# euu.net
KiCad netlist of a schematic drawn in Altium Designer
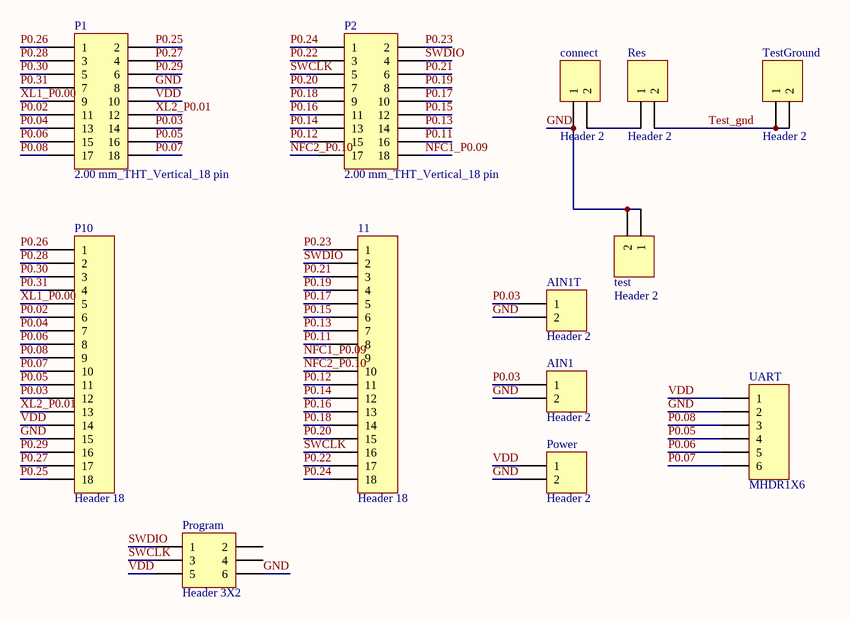
[diagram p0: euu.SchDoc]

(export (version "E")
  (design (tool "Eeschema 10.0.6"))
  (components
    (comp (ref "11")
      (value "Header 18")
      (footprint "HDR1X18")
      (description "Header, 18-Pin")
      (fields (field (name "PUBLISHER") "Altium Limited"))
      (libsource (lib "Miscellaneous Connectors") (part "Header 18"))
    )
    (comp (ref "AIN1")
      (value "Header 2")
      (footprint "HDR1X2")
      (description "Header, 2-Pin")
      (fields (field (name "PUBLISHER") "Altium Limited"))
      (libsource (lib "") (part "Header 2_1"))
    )
    (comp (ref "AIN1T")
      (value "Header 2")
      (footprint "HDR1X2")
      (description "Header, 2-Pin")
      (fields (field (name "PUBLISHER") "Altium Limited"))
      (libsource (lib "") (part "Header 2_1"))
    )
    (comp (ref "connect")
      (value "Header 2")
      (footprint "HDR1X2")
      (description "Header, 2-Pin")
      (fields (field (name "PUBLISHER") "Altium Limited"))
      (libsource (lib "Miscellaneous Connectors") (part "Header 2"))
    )
    (comp (ref "P1")
      (value "2.00 mm_THT_Vertical_18 pin")
      (footprint "header:Header9x2")
      (description "Header, 9-Pin, Dual row")
      (fields (field (name "PUBLISHER") "Altium Limited"))
      (libsource (lib "Miscellaneous Connectors") (part "Header 9X2"))
    )
    (comp (ref "P2")
      (value "2.00 mm_THT_Vertical_18 pin")
      (footprint "header:Header9x2")
      (description "Header, 9-Pin, Dual row")
      (fields (field (name "PUBLISHER") "Altium Limited"))
      (libsource (lib "Miscellaneous Connectors") (part "Header 9X2"))
    )
    (comp (ref "P10")
      (value "Header 18")
      (footprint "HDR1X18")
      (description "Header, 18-Pin")
      (fields (field (name "PUBLISHER") "Altium Limited"))
      (libsource (lib "Miscellaneous Connectors") (part "Header 18"))
    )
    (comp (ref "Power")
      (value "Header 2")
      (footprint "HDR1X2")
      (description "Header, 2-Pin")
      (fields (field (name "PUBLISHER") "Altium Limited"))
      (libsource (lib "") (part "Header 2_1"))
    )
    (comp (ref "Program")
      (value "Header 3X2")
      (footprint "HDR2X3")
      (description "Header, 3-Pin, Dual row")
      (fields (field (name "PUBLISHER") "Altium Limited"))
      (libsource (lib "Miscellaneous Connectors") (part "Header 3X2"))
    )
    (comp (ref "Res")
      (value "Header 2")
      (footprint "HDR1X2")
      (description "Header, 2-Pin")
      (fields (field (name "PUBLISHER") "Altium Limited"))
      (libsource (lib "Miscellaneous Connectors") (part "Header 2"))
    )
    (comp (ref "test")
      (value "Header 2")
      (footprint "HDR1X2")
      (description "Header, 2-Pin")
      (fields (field (name "PUBLISHER") "Altium Limited"))
      (libsource (lib "") (part "Header 2_2"))
    )
    (comp (ref "TestGround")
      (value "Header 2")
      (footprint "HDR1X2")
      (description "Header, 2-Pin")
      (fields (field (name "PUBLISHER") "Altium Limited"))
      (libsource (lib "Miscellaneous Connectors") (part "Header 2"))
    )
    (comp (ref "UART")
      (value "MHDR1X6")
      (footprint "header:HEADER6")
      (description "Header, 6-Pin")
      (fields (field (name "PUBLISHER") "Altium Limited"))
      (libsource (lib "Miscellaneous Connectors") (part "MHDR1X6"))
    )
  )
  (nets
    (net (code "1") (name "/GND") (class "Default")
      (node (ref "AIN1") (pin "2") (pinfunction "2_2") (pintype "passive"))
      (node (ref "AIN1T") (pin "2") (pinfunction "2_2") (pintype "passive"))
      (node (ref "P1") (pin "8") (pinfunction "8_8") (pintype "passive"))
      (node (ref "P10") (pin "15") (pinfunction "15_15") (pintype "passive"))
      (node (ref "Power") (pin "2") (pinfunction "2_2") (pintype "passive"))
      (node (ref "Program") (pin "6") (pinfunction "6_6") (pintype "passive"))
      (node (ref "UART") (pin "2") (pinfunction "2_2") (pintype "passive"))
      (node (ref "connect") (pin "1") (pinfunction "1_1") (pintype "passive"))
      (node (ref "test") (pin "1") (pinfunction "1_1") (pintype "passive"))
      (node (ref "test") (pin "2") (pinfunction "2_2") (pintype "passive"))
    )
    (net (code "2") (name "/NFC1_P0.09") (class "Default")
      (node (ref "11") (pin "9") (pinfunction "9_9") (pintype "passive"))
      (node (ref "P2") (pin "18") (pinfunction "18_18") (pintype "passive"))
    )
    (net (code "3") (name "/NFC2_P0.10") (class "Default")
      (node (ref "11") (pin "10") (pinfunction "10_10") (pintype "passive"))
      (node (ref "P2") (pin "17") (pinfunction "17_17") (pintype "passive"))
    )
    (net (code "4") (name "/P0.02") (class "Default")
      (node (ref "P1") (pin "11") (pinfunction "11_11") (pintype "passive"))
      (node (ref "P10") (pin "6") (pinfunction "6_6") (pintype "passive"))
    )
    (net (code "5") (name "/P0.03") (class "Default")
      (node (ref "AIN1") (pin "1") (pinfunction "1_1") (pintype "passive"))
      (node (ref "AIN1T") (pin "1") (pinfunction "1_1") (pintype "passive"))
      (node (ref "P1") (pin "14") (pinfunction "14_14") (pintype "passive"))
      (node (ref "P10") (pin "12") (pinfunction "12_12") (pintype "passive"))
    )
    (net (code "6") (name "/P0.04") (class "Default")
      (node (ref "P1") (pin "13") (pinfunction "13_13") (pintype "passive"))
      (node (ref "P10") (pin "7") (pinfunction "7_7") (pintype "passive"))
    )
    (net (code "7") (name "/P0.05") (class "Default")
      (node (ref "P1") (pin "16") (pinfunction "16_16") (pintype "passive"))
      (node (ref "P10") (pin "11") (pinfunction "11_11") (pintype "passive"))
      (node (ref "UART") (pin "4") (pinfunction "4_4") (pintype "passive"))
    )
    (net (code "8") (name "/P0.06") (class "Default")
      (node (ref "P1") (pin "15") (pinfunction "15_15") (pintype "passive"))
      (node (ref "P10") (pin "8") (pinfunction "8_8") (pintype "passive"))
      (node (ref "UART") (pin "5") (pinfunction "5_5") (pintype "passive"))
    )
    (net (code "9") (name "/P0.07") (class "Default")
      (node (ref "P1") (pin "18") (pinfunction "18_18") (pintype "passive"))
      (node (ref "P10") (pin "10") (pinfunction "10_10") (pintype "passive"))
      (node (ref "UART") (pin "6") (pinfunction "6_6") (pintype "passive"))
    )
    (net (code "10") (name "/P0.08") (class "Default")
      (node (ref "P1") (pin "17") (pinfunction "17_17") (pintype "passive"))
      (node (ref "P10") (pin "9") (pinfunction "9_9") (pintype "passive"))
      (node (ref "UART") (pin "3") (pinfunction "3_3") (pintype "passive"))
    )
    (net (code "11") (name "/P0.11") (class "Default")
      (node (ref "11") (pin "8") (pinfunction "8_8") (pintype "passive"))
      (node (ref "P2") (pin "16") (pinfunction "16_16") (pintype "passive"))
    )
    (net (code "12") (name "/P0.12") (class "Default")
      (node (ref "11") (pin "11") (pinfunction "11_11") (pintype "passive"))
      (node (ref "P2") (pin "15") (pinfunction "15_15") (pintype "passive"))
    )
    (net (code "13") (name "/P0.13") (class "Default")
      (node (ref "11") (pin "7") (pinfunction "7_7") (pintype "passive"))
      (node (ref "P2") (pin "14") (pinfunction "14_14") (pintype "passive"))
    )
    (net (code "14") (name "/P0.14") (class "Default")
      (node (ref "11") (pin "12") (pinfunction "12_12") (pintype "passive"))
      (node (ref "P2") (pin "13") (pinfunction "13_13") (pintype "passive"))
    )
    (net (code "15") (name "/P0.15") (class "Default")
      (node (ref "11") (pin "6") (pinfunction "6_6") (pintype "passive"))
      (node (ref "P2") (pin "12") (pinfunction "12_12") (pintype "passive"))
    )
    (net (code "16") (name "/P0.16") (class "Default")
      (node (ref "11") (pin "13") (pinfunction "13_13") (pintype "passive"))
      (node (ref "P2") (pin "11") (pinfunction "11_11") (pintype "passive"))
    )
    (net (code "17") (name "/P0.17") (class "Default")
      (node (ref "11") (pin "5") (pinfunction "5_5") (pintype "passive"))
      (node (ref "P2") (pin "10") (pinfunction "10_10") (pintype "passive"))
    )
    (net (code "18") (name "/P0.18") (class "Default")
      (node (ref "11") (pin "14") (pinfunction "14_14") (pintype "passive"))
      (node (ref "P2") (pin "9") (pinfunction "9_9") (pintype "passive"))
    )
    (net (code "19") (name "/P0.19") (class "Default")
      (node (ref "11") (pin "4") (pinfunction "4_4") (pintype "passive"))
      (node (ref "P2") (pin "8") (pinfunction "8_8") (pintype "passive"))
    )
    (net (code "20") (name "/P0.20") (class "Default")
      (node (ref "11") (pin "15") (pinfunction "15_15") (pintype "passive"))
      (node (ref "P2") (pin "7") (pinfunction "7_7") (pintype "passive"))
    )
    (net (code "21") (name "/P0.21") (class "Default")
      (node (ref "11") (pin "3") (pinfunction "3_3") (pintype "passive"))
      (node (ref "P2") (pin "6") (pinfunction "6_6") (pintype "passive"))
    )
    (net (code "22") (name "/P0.22") (class "Default")
      (node (ref "11") (pin "17") (pinfunction "17_17") (pintype "passive"))
      (node (ref "P2") (pin "3") (pinfunction "3_3") (pintype "passive"))
    )
    (net (code "23") (name "/P0.23") (class "Default")
      (node (ref "11") (pin "1") (pinfunction "1_1") (pintype "passive"))
      (node (ref "P2") (pin "2") (pinfunction "2_2") (pintype "passive"))
    )
    (net (code "24") (name "/P0.24") (class "Default")
      (node (ref "11") (pin "18") (pinfunction "18_18") (pintype "passive"))
      (node (ref "P2") (pin "1") (pinfunction "1_1") (pintype "passive"))
    )
    (net (code "25") (name "/P0.25") (class "Default")
      (node (ref "P1") (pin "2") (pinfunction "2_2") (pintype "passive"))
      (node (ref "P10") (pin "18") (pinfunction "18_18") (pintype "passive"))
    )
    (net (code "26") (name "/P0.26") (class "Default")
      (node (ref "P1") (pin "1") (pinfunction "1_1") (pintype "passive"))
      (node (ref "P10") (pin "1") (pinfunction "1_1") (pintype "passive"))
    )
    (net (code "27") (name "/P0.27") (class "Default")
      (node (ref "P1") (pin "4") (pinfunction "4_4") (pintype "passive"))
      (node (ref "P10") (pin "17") (pinfunction "17_17") (pintype "passive"))
    )
    (net (code "28") (name "/P0.28") (class "Default")
      (node (ref "P1") (pin "3") (pinfunction "3_3") (pintype "passive"))
      (node (ref "P10") (pin "2") (pinfunction "2_2") (pintype "passive"))
    )
    (net (code "29") (name "/P0.29") (class "Default")
      (node (ref "P1") (pin "6") (pinfunction "6_6") (pintype "passive"))
      (node (ref "P10") (pin "16") (pinfunction "16_16") (pintype "passive"))
    )
    (net (code "30") (name "/P0.30") (class "Default")
      (node (ref "P1") (pin "5") (pinfunction "5_5") (pintype "passive"))
      (node (ref "P10") (pin "3") (pinfunction "3_3") (pintype "passive"))
    )
    (net (code "31") (name "/P0.31") (class "Default")
      (node (ref "P1") (pin "7") (pinfunction "7_7") (pintype "passive"))
      (node (ref "P10") (pin "4") (pinfunction "4_4") (pintype "passive"))
    )
    (net (code "32") (name "/SWCLK") (class "Default")
      (node (ref "11") (pin "16") (pinfunction "16_16") (pintype "passive"))
      (node (ref "P2") (pin "5") (pinfunction "5_5") (pintype "passive"))
      (node (ref "Program") (pin "3") (pinfunction "3_3") (pintype "passive"))
    )
    (net (code "33") (name "/SWDIO") (class "Default")
      (node (ref "11") (pin "2") (pinfunction "2_2") (pintype "passive"))
      (node (ref "P2") (pin "4") (pinfunction "4_4") (pintype "passive"))
      (node (ref "Program") (pin "1") (pinfunction "1_1") (pintype "passive"))
    )
    (net (code "34") (name "/Test_gnd") (class "Default")
      (node (ref "Res") (pin "2") (pinfunction "2_2") (pintype "passive"))
      (node (ref "TestGround") (pin "1") (pinfunction "1_1") (pintype "passive"))
      (node (ref "TestGround") (pin "2") (pinfunction "2_2") (pintype "passive"))
    )
    (net (code "35") (name "/VDD") (class "Default")
      (node (ref "P1") (pin "10") (pinfunction "10_10") (pintype "passive"))
      (node (ref "P10") (pin "14") (pinfunction "14_14") (pintype "passive"))
      (node (ref "Power") (pin "1") (pinfunction "1_1") (pintype "passive"))
      (node (ref "Program") (pin "5") (pinfunction "5_5") (pintype "passive"))
      (node (ref "UART") (pin "1") (pinfunction "1_1") (pintype "passive"))
    )
    (net (code "36") (name "/XL1_P0.00") (class "Default")
      (node (ref "P1") (pin "9") (pinfunction "9_9") (pintype "passive"))
      (node (ref "P10") (pin "5") (pinfunction "5_5") (pintype "passive"))
    )
    (net (code "37") (name "/XL2_P0.01") (class "Default")
      (node (ref "P1") (pin "12") (pinfunction "12_12") (pintype "passive"))
      (node (ref "P10") (pin "13") (pinfunction "13_13") (pintype "passive"))
    )
    (net (code "38") (name "Net-(Res-Pad1)") (class "Default")
      (node (ref "Res") (pin "1") (pinfunction "1_1") (pintype "passive"))
      (node (ref "connect") (pin "2") (pinfunction "2_2") (pintype "passive"))
    )
    (net (code "39") (name "unconnected-(Program-Pad2)") (class "Default")
      (node (ref "Program") (pin "2") (pinfunction "2_2") (pintype "passive"))
    )
    (net (code "40") (name "unconnected-(Program-Pad4)") (class "Default")
      (node (ref "Program") (pin "4") (pinfunction "4_4") (pintype "passive"))
    )
  )
)
